# 07_CAMERA-MIPI.net
KiCad netlist of a schematic drawn in Altium Designer
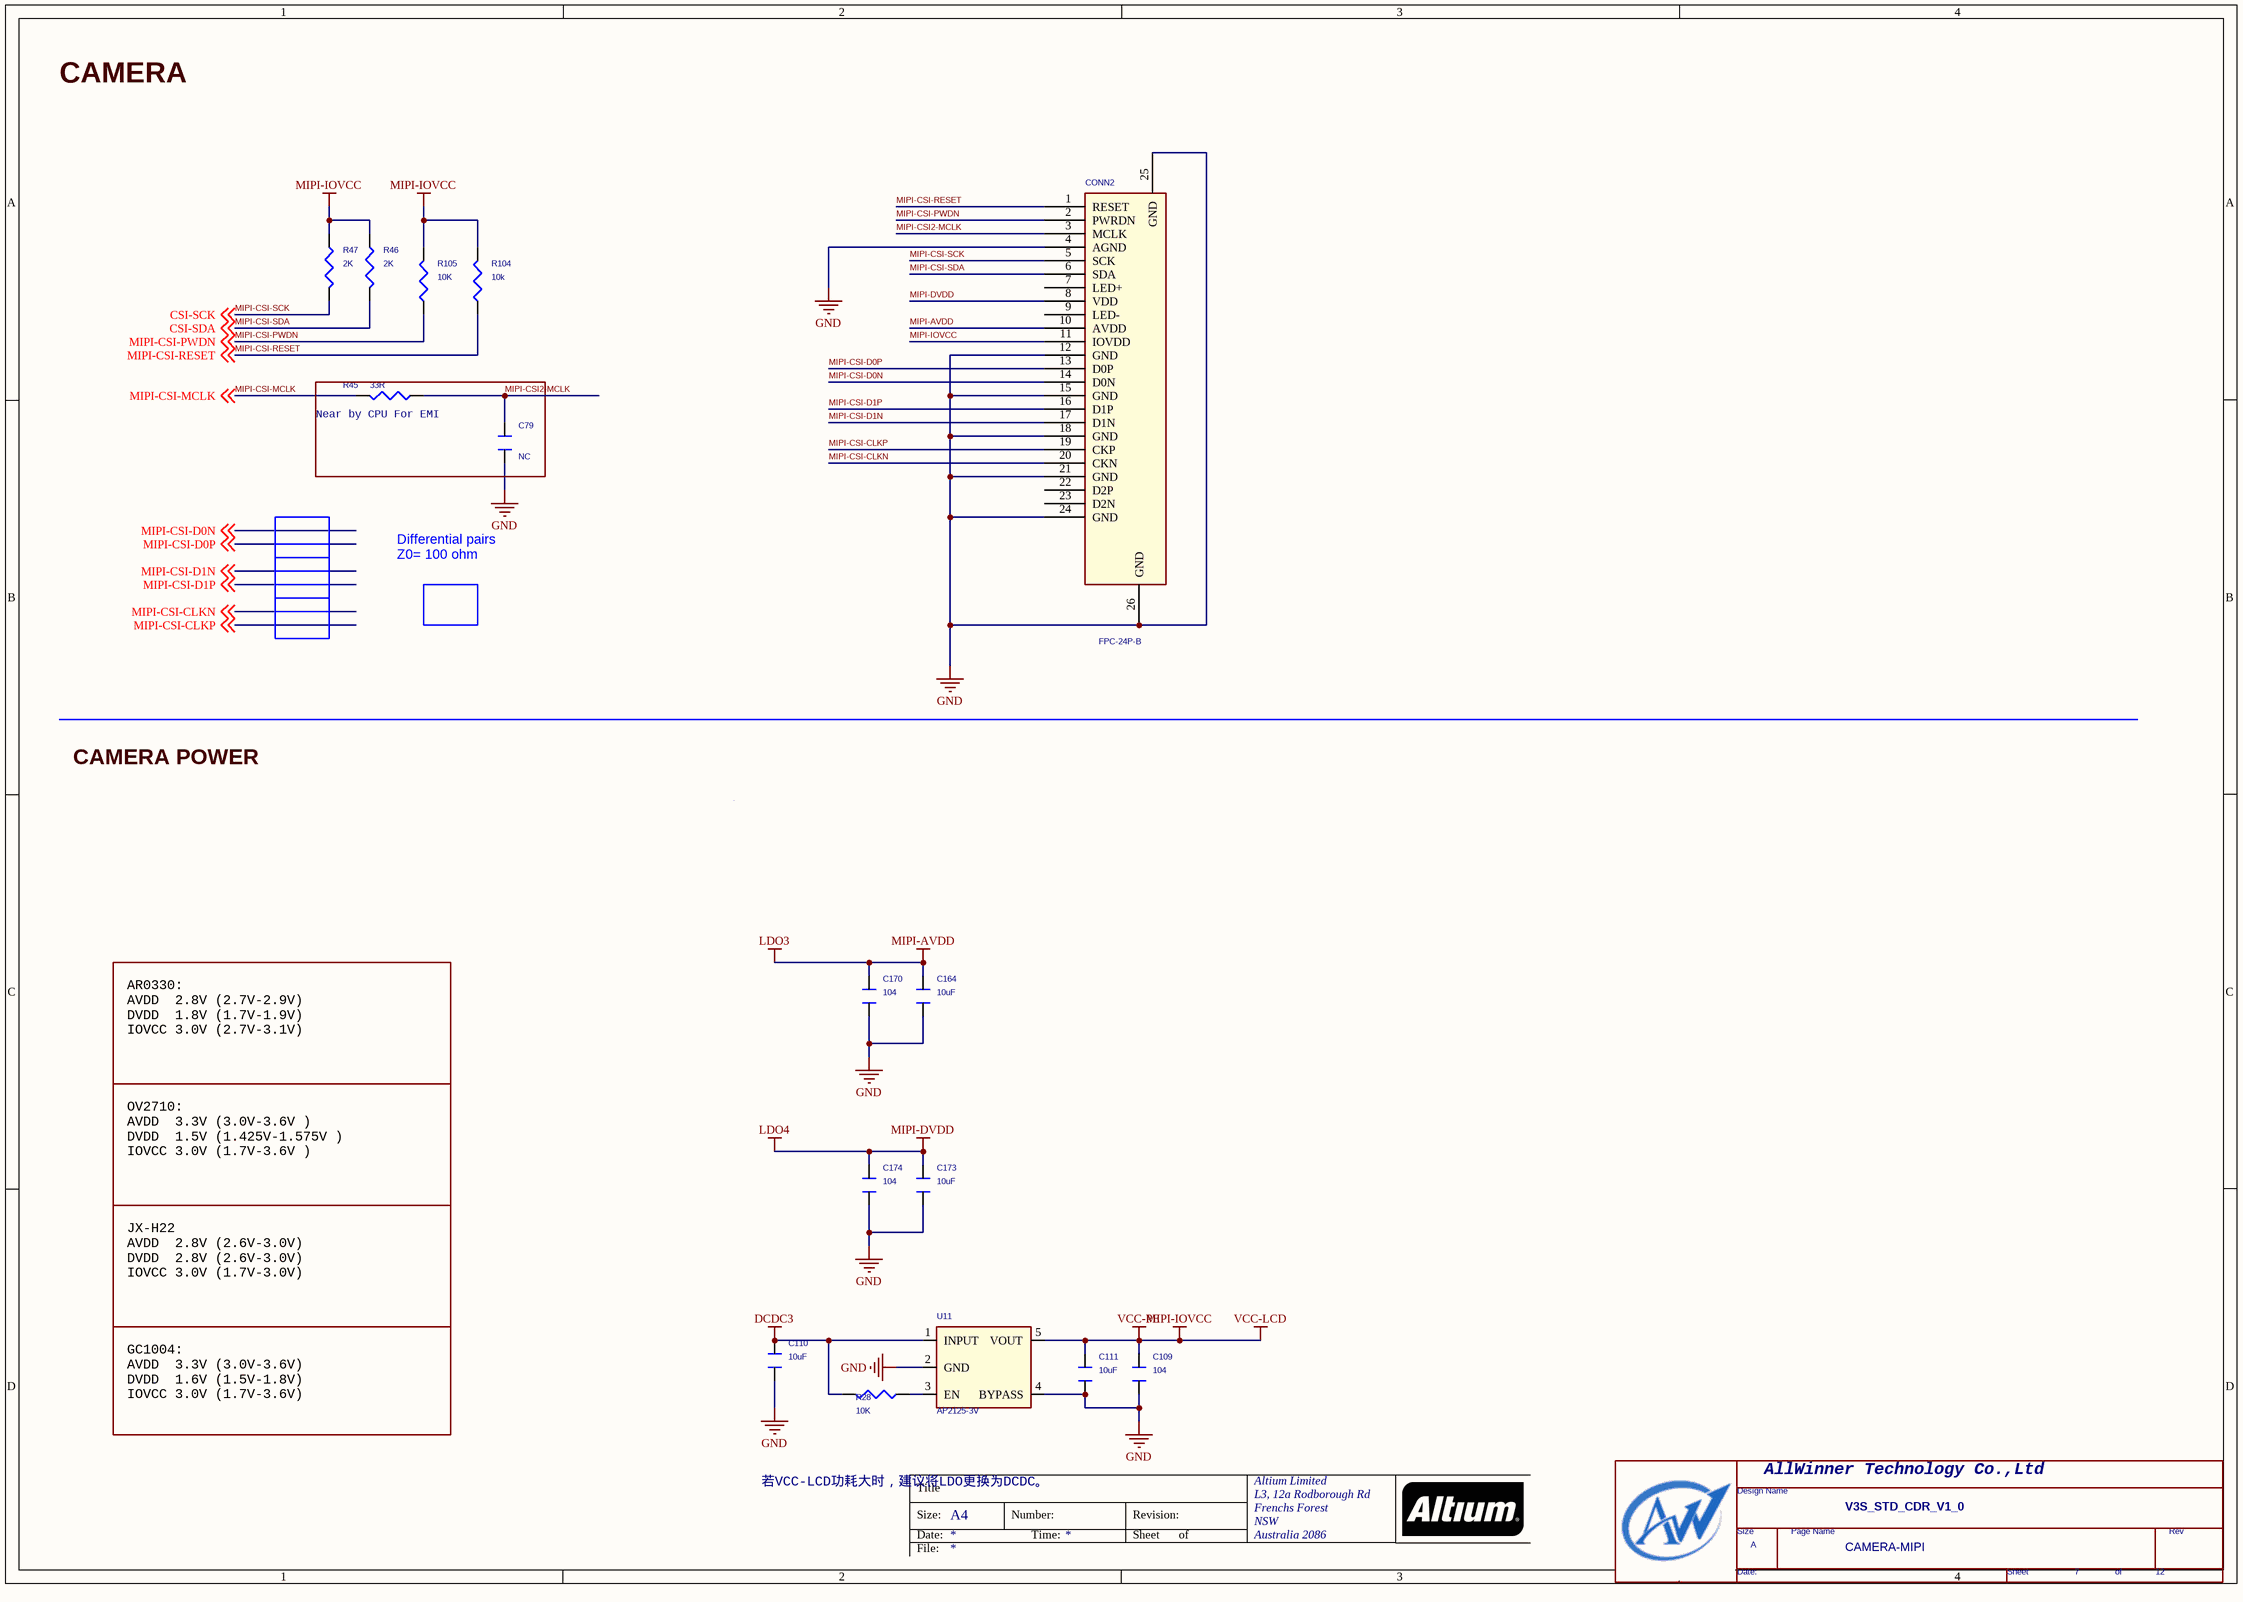
[diagram p0: 07 CAMERA-MIPI.SchDoc]

(export (version "E")
  (design (tool "Eeschema 10.0.6"))
  (components
    (comp (ref "C79") (value "NC") (footprint "C0402") (libsource (lib "*") (part "CAPACITOR_0_Dup5")))
    (comp (ref "C109") (value "104") (footprint "C0402") (libsource (lib "*") (part "CAPACITOR_0_Dup5")))
    (comp (ref "C110") (value "10uF") (footprint "C0603") (libsource (lib "*") (part "CAPACITOR_2")))
    (comp (ref "C111") (value "10uF") (footprint "C0603") (libsource (lib "*") (part "CAPACITOR_2")))
    (comp (ref "C164") (value "10uF") (footprint "C0603") (libsource (lib "*") (part "CAPACITOR_2")))
    (comp (ref "C170") (value "104") (footprint "C0402") (libsource (lib "*") (part "CAPACITOR_0_Dup5")))
    (comp (ref "C173") (value "10uF") (footprint "C0603") (libsource (lib "*") (part "CAPACITOR_2")))
    (comp (ref "C174") (value "104") (footprint "C0402") (libsource (lib "*") (part "CAPACITOR_0_Dup5")))
    (comp (ref "CONN2") (value "FPC-24P-B") (footprint "CON40") (libsource (lib "*") (part "TD030673_2")))
    (comp (ref "R28") (value "10K") (footprint "R0402") (libsource (lib "*") (part "R_Dup4")))
    (comp (ref "R45") (value "33R") (footprint "R0603") (libsource (lib "*") (part "RESISTOR_0")))
    (comp (ref "R46") (value "2K") (footprint "R0402") (libsource (lib "*") (part "R_Dup4")))
    (comp (ref "R47") (value "2K") (footprint "R0402") (libsource (lib "*") (part "R_Dup4")))
    (comp (ref "R104") (value "10k") (footprint "R0402") (libsource (lib "*") (part "R_Dup3")))
    (comp (ref "R105") (value "10K") (footprint "R0402") (libsource (lib "*") (part "R_Dup3")))
    (comp (ref "U11")
      (value "AP2125-3V")
      (footprint "SOT23-5")
      (libsource (lib "*") (part "LP3985IM5-3_2.3"))
    )
  )
  (nets
    (net (code "1") (name "/MIPI-CSI2-MCLK") (class "Default")
      (node (ref "C79") (pin "2") (pinfunction "2_2") (pintype "passive"))
      (node (ref "CONN2") (pin "3") (pinfunction "MCLK_3") (pintype "passive"))
      (node (ref "R45") (pin "1") (pinfunction "1_1") (pintype "passive"))
    )
    (net (code "2") (name "CSI-SCK") (class "Default")
      (node (ref "CONN2") (pin "5") (pinfunction "SCK_5") (pintype "passive"))
      (node (ref "R47") (pin "2") (pinfunction "2_2") (pintype "passive"))
    )
    (net (code "3") (name "CSI-SDA") (class "Default")
      (node (ref "CONN2") (pin "6") (pinfunction "SDA_6") (pintype "passive"))
      (node (ref "R46") (pin "2") (pinfunction "2_2") (pintype "passive"))
    )
    (net (code "4") (name "DCDC3") (class "Default")
      (node (ref "C110") (pin "1") (pinfunction "1_1") (pintype "passive"))
      (node (ref "R28") (pin "2") (pinfunction "2_2") (pintype "passive"))
      (node (ref "U11") (pin "1") (pinfunction "INPUT_1") (pintype "passive"))
    )
    (net (code "5") (name "GND") (class "Default")
      (node (ref "C109") (pin "1") (pinfunction "1_1") (pintype "passive"))
      (node (ref "C110") (pin "2") (pinfunction "2_2") (pintype "passive"))
      (node (ref "C111") (pin "2") (pinfunction "2_2") (pintype "passive"))
      (node (ref "C164") (pin "2") (pinfunction "2_2") (pintype "passive"))
      (node (ref "C170") (pin "1") (pinfunction "1_1") (pintype "passive"))
      (node (ref "C173") (pin "2") (pinfunction "2_2") (pintype "passive"))
      (node (ref "C174") (pin "1") (pinfunction "1_1") (pintype "passive"))
      (node (ref "C79") (pin "1") (pinfunction "1_1") (pintype "passive"))
      (node (ref "CONN2") (pin "12") (pinfunction "GND_12") (pintype "passive"))
      (node (ref "CONN2") (pin "15") (pinfunction "GND_15") (pintype "passive"))
      (node (ref "CONN2") (pin "18") (pinfunction "GND_18") (pintype "passive"))
      (node (ref "CONN2") (pin "21") (pinfunction "GND_21") (pintype "passive"))
      (node (ref "CONN2") (pin "24") (pinfunction "GND_24") (pintype "passive"))
      (node (ref "CONN2") (pin "25") (pinfunction "GND_25") (pintype "passive"))
      (node (ref "CONN2") (pin "26") (pinfunction "GND_26") (pintype "passive"))
      (node (ref "CONN2") (pin "4") (pinfunction "AGND_4") (pintype "passive"))
      (node (ref "U11") (pin "2") (pinfunction "GND_2") (pintype "passive"))
      (node (ref "U11") (pin "4") (pinfunction "BYPASS_4") (pintype "passive"))
    )
    (net (code "6") (name "LDO3") (class "Default")
      (node (ref "C164") (pin "1") (pinfunction "1_1") (pintype "passive"))
      (node (ref "C170") (pin "2") (pinfunction "2_2") (pintype "passive"))
      (node (ref "CONN2") (pin "10") (pinfunction "AVDD_10") (pintype "passive"))
    )
    (net (code "7") (name "LDO4") (class "Default")
      (node (ref "C173") (pin "1") (pinfunction "1_1") (pintype "passive"))
      (node (ref "C174") (pin "2") (pinfunction "2_2") (pintype "passive"))
      (node (ref "CONN2") (pin "8") (pinfunction "VDD_8") (pintype "passive"))
    )
    (net (code "8") (name "MIPI-CSI-CLKN") (class "Default")
      (node (ref "CONN2") (pin "20") (pinfunction "CKN_20") (pintype "passive"))
    )
    (net (code "9") (name "MIPI-CSI-CLKP") (class "Default")
      (node (ref "CONN2") (pin "19") (pinfunction "CKP_19") (pintype "passive"))
    )
    (net (code "10") (name "MIPI-CSI-D0N") (class "Default")
      (node (ref "CONN2") (pin "14") (pinfunction "D0N_14") (pintype "passive"))
    )
    (net (code "11") (name "MIPI-CSI-D0P") (class "Default")
      (node (ref "CONN2") (pin "13") (pinfunction "D0P_13") (pintype "passive"))
    )
    (net (code "12") (name "MIPI-CSI-D1N") (class "Default")
      (node (ref "CONN2") (pin "17") (pinfunction "D1N_17") (pintype "passive"))
    )
    (net (code "13") (name "MIPI-CSI-D1P") (class "Default")
      (node (ref "CONN2") (pin "16") (pinfunction "D1P_16") (pintype "passive"))
    )
    (net (code "14") (name "MIPI-CSI-MCLK") (class "Default")
      (node (ref "R45") (pin "2") (pinfunction "2_2") (pintype "passive"))
    )
    (net (code "15") (name "MIPI-CSI-PWDN") (class "Default")
      (node (ref "CONN2") (pin "2") (pinfunction "PWRDN_2") (pintype "passive"))
      (node (ref "R105") (pin "1") (pinfunction "1_1") (pintype "passive"))
    )
    (net (code "16") (name "MIPI-CSI-RESET") (class "Default")
      (node (ref "CONN2") (pin "1") (pinfunction "RESET_1") (pintype "passive"))
      (node (ref "R104") (pin "1") (pinfunction "1_1") (pintype "passive"))
    )
    (net (code "17") (name "MIPI-IOVCC") (class "Default")
      (node (ref "C109") (pin "2") (pinfunction "2_2") (pintype "passive"))
      (node (ref "C111") (pin "1") (pinfunction "1_1") (pintype "passive"))
      (node (ref "CONN2") (pin "11") (pinfunction "IOVDD_11") (pintype "passive"))
      (node (ref "R104") (pin "2") (pinfunction "2_2") (pintype "passive"))
      (node (ref "R105") (pin "2") (pinfunction "2_2") (pintype "passive"))
      (node (ref "R46") (pin "1") (pinfunction "1_1") (pintype "passive"))
      (node (ref "R47") (pin "1") (pinfunction "1_1") (pintype "passive"))
      (node (ref "U11") (pin "5") (pinfunction "VOUT_5") (pintype "passive"))
    )
    (net (code "18") (name "Net-(U11-EN)") (class "Default")
      (node (ref "R28") (pin "1") (pinfunction "1_1") (pintype "passive"))
      (node (ref "U11") (pin "3") (pinfunction "EN_3") (pintype "passive"))
    )
    (net (code "19") (name "unconnected-(CONN2-D2N-Pad23)") (class "Default")
      (node (ref "CONN2") (pin "23") (pinfunction "D2N_23") (pintype "passive"))
    )
    (net (code "20") (name "unconnected-(CONN2-D2P-Pad22)") (class "Default")
      (node (ref "CONN2") (pin "22") (pinfunction "D2P_22") (pintype "passive"))
    )
    (net (code "21") (name "unconnected-(CONN2-LED+-Pad7)") (class "Default")
      (node (ref "CONN2") (pin "7") (pinfunction "LED+_7") (pintype "passive"))
    )
    (net (code "22") (name "unconnected-(CONN2-LED--Pad9)") (class "Default")
      (node (ref "CONN2") (pin "9") (pinfunction "LED-_9") (pintype "passive"))
    )
  )
)
